# AT42QT2120-breakout.net
KiCad netlist of a schematic drawn in EAGLE
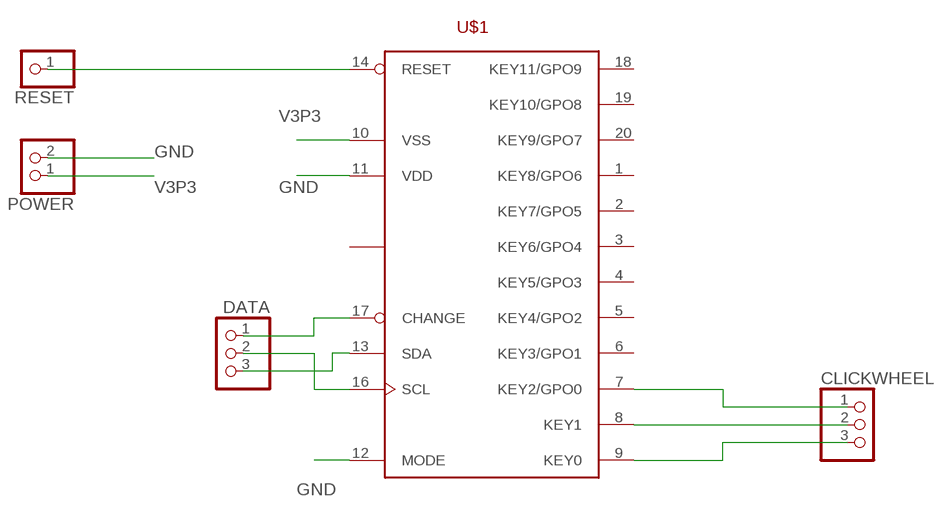
[diagram p0: schematic, sheet 1]

(export (version "E")
  (design (tool "Eeschema 10.0.6"))
  (components
    (comp (ref "CLICKWHEEL")
      (value "PINHD-1X3/90")
      (footprint "eagle-import:1X03_90")
      (libsource (lib "eagle-import") (part "PINHD-1X3/90"))
    )
    (comp (ref "DATA")
      (value "PINHD-1X3/90")
      (footprint "eagle-import:1X03_90")
      (libsource (lib "eagle-import") (part "PINHD-1X3/90"))
    )
    (comp (ref "POWER")
      (value "PINHD-1X2/90")
      (footprint "eagle-import:1X02_90")
      (libsource (lib "eagle-import") (part "PINHD-1X2/90"))
    )
    (comp (ref "RESET")
      (value "PINHD-1X1")
      (footprint "eagle-import:1X01")
      (libsource (lib "eagle-import") (part "PINHD-1X1"))
    )
    (comp (ref "U$1")
      (value "COMMS-AT42QT2120SU")
      (footprint "eagle-import:SO20W")
      (libsource (lib "eagle-import") (part "COMMS-AT42QT2120SU"))
    )
  )
  (nets
    (net (code "1") (name "/GND") (class "Default")
      (node (ref "POWER") (pin "2") (pinfunction "2_2") (pintype "passive"))
      (node (ref "U$1") (pin "11") (pinfunction "VDD_11") (pintype "power_in"))
      (node (ref "U$1") (pin "12") (pinfunction "MODE_12") (pintype "input"))
    )
    (net (code "2") (name "/V3P3") (class "Default")
      (node (ref "POWER") (pin "1") (pinfunction "1_1") (pintype "passive"))
      (node (ref "U$1") (pin "10") (pinfunction "VSS_10") (pintype "power_in"))
    )
    (net (code "3") (name "Net-(U$1-CHANGE)") (class "Default")
      (node (ref "DATA") (pin "1") (pinfunction "1_1") (pintype "passive"))
      (node (ref "U$1") (pin "17") (pinfunction "CHANGE_17") (pintype "open_collector"))
    )
    (net (code "4") (name "Net-(U$1-KEY0)") (class "Default")
      (node (ref "CLICKWHEEL") (pin "3") (pinfunction "3_3") (pintype "passive"))
      (node (ref "U$1") (pin "9") (pinfunction "KEY0_9") (pintype "bidirectional"))
    )
    (net (code "5") (name "Net-(U$1-KEY1)") (class "Default")
      (node (ref "CLICKWHEEL") (pin "2") (pinfunction "2_2") (pintype "passive"))
      (node (ref "U$1") (pin "8") (pinfunction "KEY1_8") (pintype "bidirectional"))
    )
    (net (code "6") (name "Net-(U$1-KEY2{slash}GPO0)") (class "Default")
      (node (ref "CLICKWHEEL") (pin "1") (pinfunction "1_1") (pintype "passive"))
      (node (ref "U$1") (pin "7") (pinfunction "KEY2/GPO0_7") (pintype "bidirectional"))
    )
    (net (code "7") (name "Net-(U$1-RESET)") (class "Default")
      (node (ref "RESET") (pin "1") (pinfunction "1_1") (pintype "passive"))
      (node (ref "U$1") (pin "14") (pinfunction "RESET_14") (pintype "input"))
    )
    (net (code "8") (name "Net-(U$1-SCL)") (class "Default")
      (node (ref "DATA") (pin "2") (pinfunction "2_2") (pintype "passive"))
      (node (ref "U$1") (pin "16") (pinfunction "SCL_16") (pintype "open_collector"))
    )
    (net (code "9") (name "Net-(U$1-SDA)") (class "Default")
      (node (ref "DATA") (pin "3") (pinfunction "3_3") (pintype "passive"))
      (node (ref "U$1") (pin "13") (pinfunction "SDA_13") (pintype "open_collector"))
    )
    (net (code "10") (name "unconnected-(U$1-KEY3{slash}GPO1-Pad6)") (class "Default")
      (node (ref "U$1") (pin "6") (pinfunction "KEY3/GPO1_6") (pintype "bidirectional"))
    )
    (net (code "11") (name "unconnected-(U$1-KEY4{slash}GPO2-Pad5)") (class "Default")
      (node (ref "U$1") (pin "5") (pinfunction "KEY4/GPO2_5") (pintype "bidirectional"))
    )
    (net (code "12") (name "unconnected-(U$1-KEY5{slash}GPO3-Pad4)") (class "Default")
      (node (ref "U$1") (pin "4") (pinfunction "KEY5/GPO3_4") (pintype "bidirectional"))
    )
    (net (code "13") (name "unconnected-(U$1-KEY6{slash}GPO4-Pad3)") (class "Default")
      (node (ref "U$1") (pin "3") (pinfunction "KEY6/GPO4_3") (pintype "bidirectional"))
    )
    (net (code "14") (name "unconnected-(U$1-KEY7{slash}GPO5-Pad2)") (class "Default")
      (node (ref "U$1") (pin "2") (pinfunction "KEY7/GPO5_2") (pintype "bidirectional"))
    )
    (net (code "15") (name "unconnected-(U$1-KEY8{slash}GPO6-Pad1)") (class "Default")
      (node (ref "U$1") (pin "1") (pinfunction "KEY8/GPO6_1") (pintype "bidirectional"))
    )
    (net (code "16") (name "unconnected-(U$1-KEY9{slash}GPO7-Pad20)") (class "Default")
      (node (ref "U$1") (pin "20") (pinfunction "KEY9/GPO7_20") (pintype "bidirectional"))
    )
    (net (code "17") (name "unconnected-(U$1-KEY10{slash}GPO8-Pad19)") (class "Default")
      (node (ref "U$1") (pin "19") (pinfunction "KEY10/GPO8_19") (pintype "bidirectional"))
    )
    (net (code "18") (name "unconnected-(U$1-KEY11{slash}GPO9-Pad18)") (class "Default")
      (node (ref "U$1") (pin "18") (pinfunction "KEY11/GPO9_18") (pintype "bidirectional"))
    )
    (net (code "19") (name "unconnected-(U$1-NC-Pad15)") (class "Default")
      (node (ref "U$1") (pin "15") (pinfunction "NC_15") (pintype "no_connect"))
    )
  )
)
